# Sheet3.net
KiCad netlist of a schematic drawn in Altium Designer
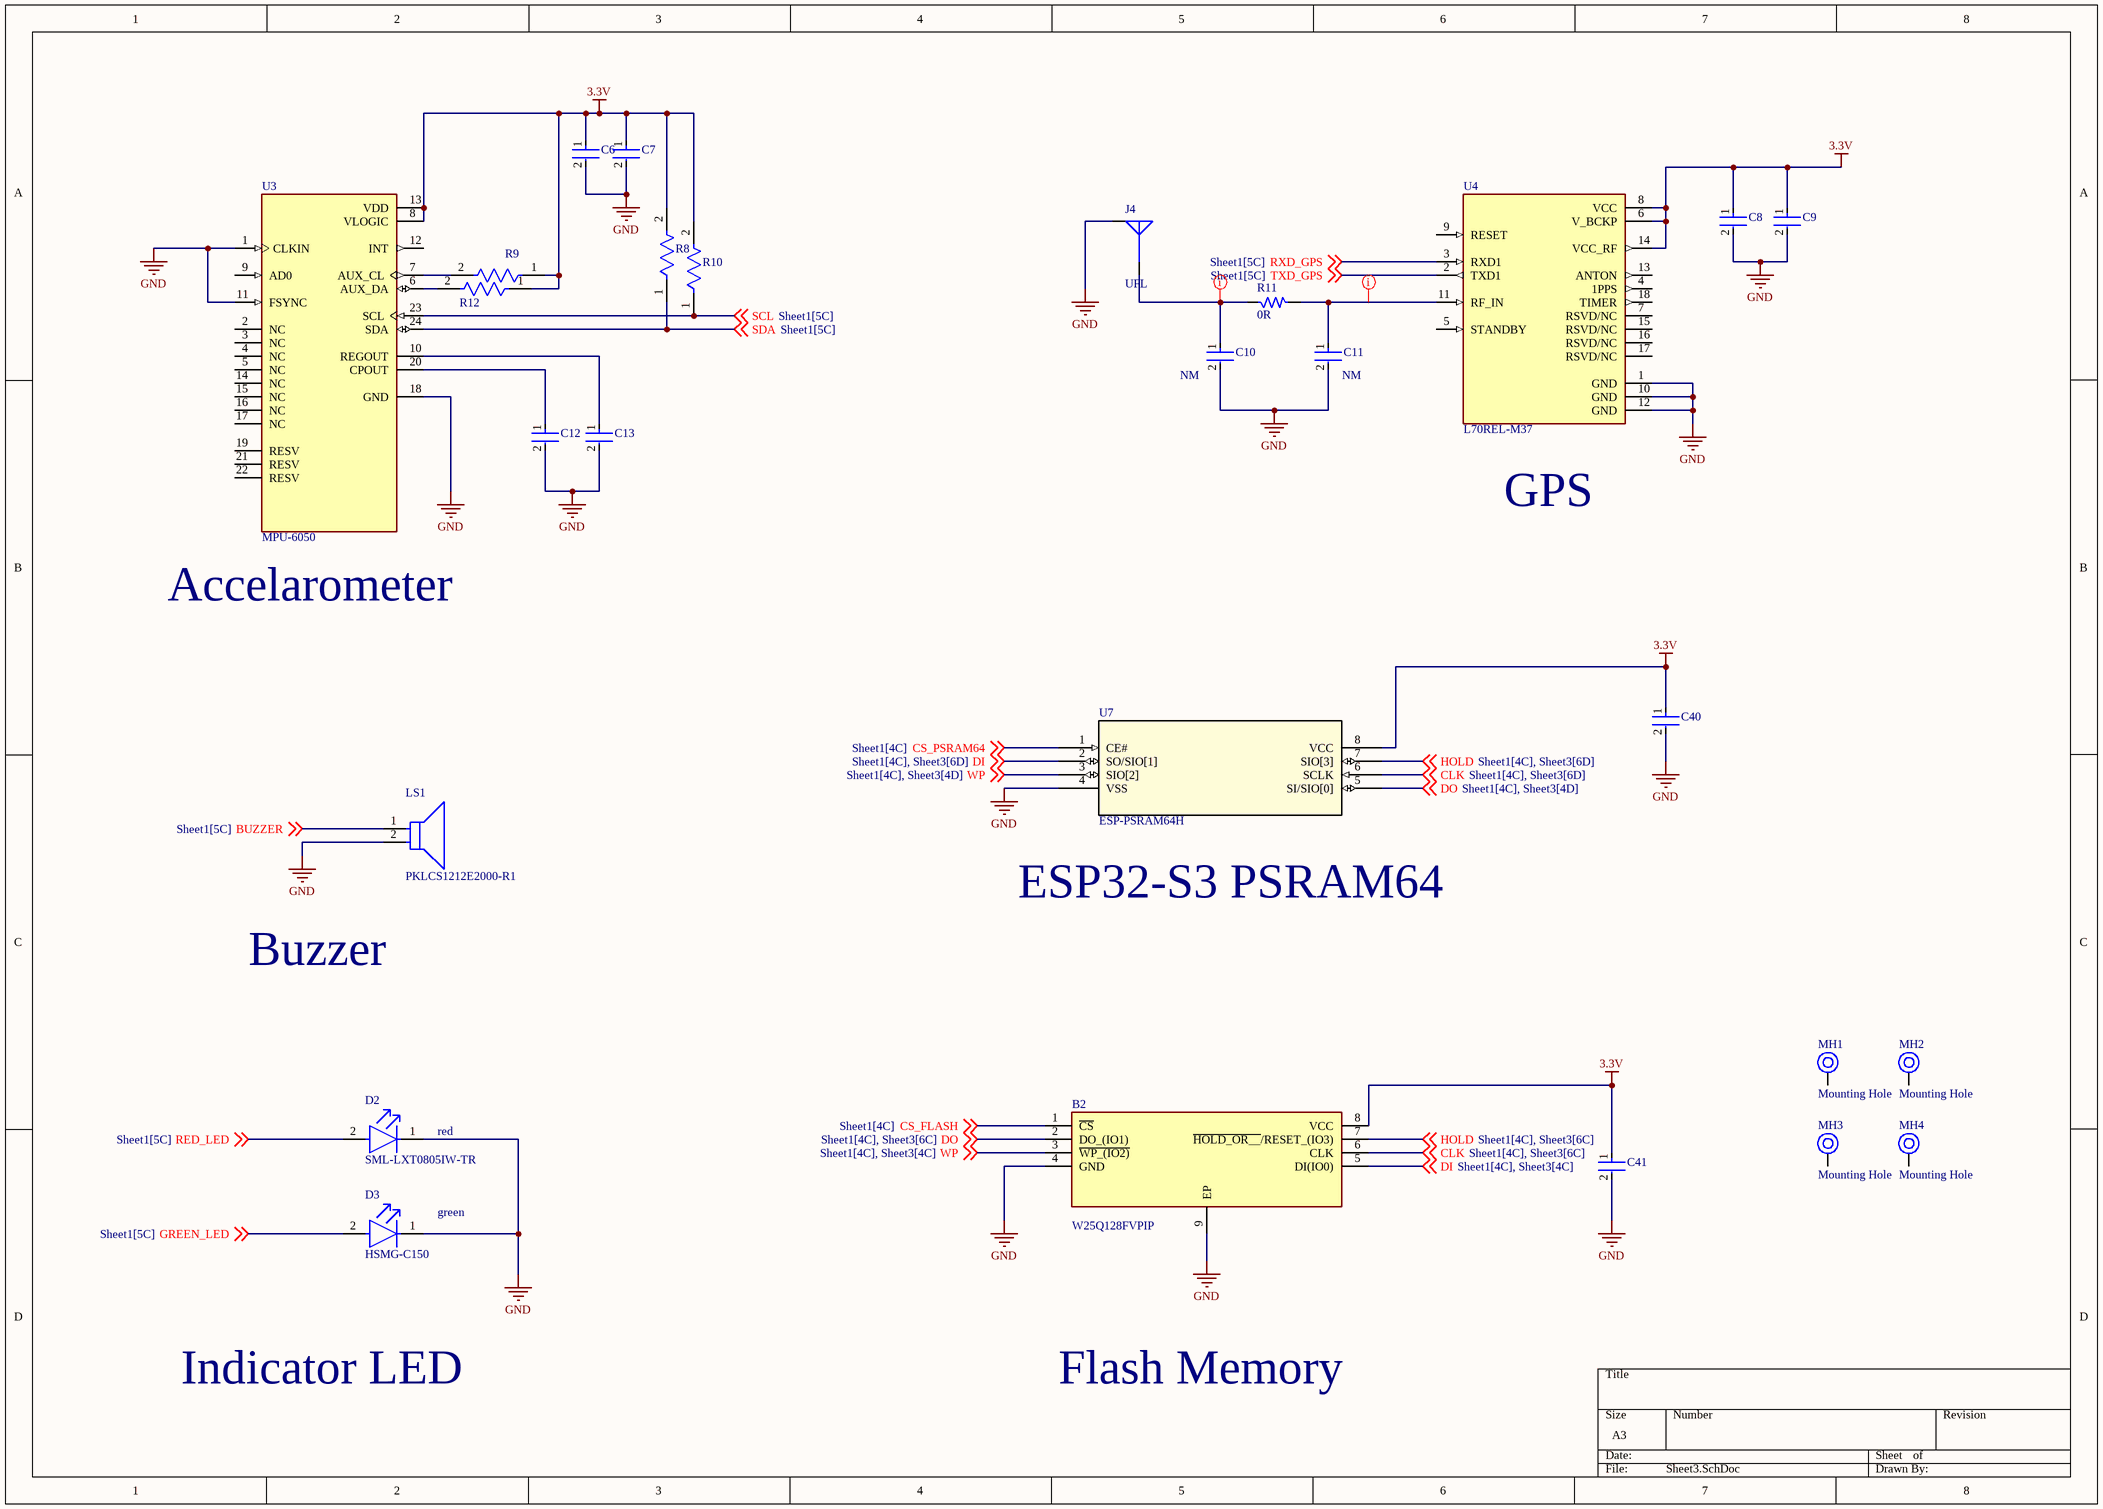
[diagram p0: Sheet3.SchDoc]

(export (version "E")
  (design (tool "Eeschema 10.0.6"))
  (components
    (comp (ref "B2")
      (value "W25Q128FVPIP")
      (footprint "SON127P600X500X80-9N-D")
      (description "3V 128M-BIT Serial Flash Memory With Dual/Quad SPI & QPI")
      (libsource (lib "W25Q128FVPIP") (part "W25Q128FVPIP"))
    )
    (comp (ref "C6")
      (value "C0402C104K4RACTU")
      (footprint "FP-C0402-BB-MFG")
      (description "CAP CER 0.1UF 16V X7R 0402")
      (fields
        (field (name "TOLERANCE") "0.1")
        (field (name "OCTOPART") "https://octopart.com/c0402c104k4ractu-kemet-94158")
      )
      (libsource (lib "Altium Content Vault") (part "b4654b650e69147ec39a6b967a45e02"))
    )
    (comp (ref "C7")
      (value "C0402C104K4RACTU")
      (footprint "FP-C0402-BB-MFG")
      (description "CAP CER 0.1UF 16V X7R 0402")
      (fields
        (field (name "TOLERANCE") "0.1")
        (field (name "OCTOPART") "https://octopart.com/c0402c104k4ractu-kemet-94158")
      )
      (libsource (lib "Altium Content Vault") (part "b4654b650e69147ec39a6b967a45e02"))
    )
    (comp (ref "C8")
      (value "C0402C104K4RACTU")
      (footprint "FP-C0402-BB-MFG")
      (description "CAP CER 0.1UF 16V X7R 0402")
      (fields
        (field (name "TOLERANCE") "0.1")
        (field (name "OCTOPART") "https://octopart.com/c0402c104k4ractu-kemet-94158")
      )
      (libsource (lib "Altium Content Vault") (part "b4654b650e69147ec39a6b967a45e02"))
    )
    (comp (ref "C9")
      (value "C0402C104K4RACTU")
      (footprint "FP-C0402-BB-MFG")
      (description "CAP CER 0.1UF 16V X7R 0402")
      (fields
        (field (name "TOLERANCE") "0.1")
        (field (name "OCTOPART") "https://octopart.com/c0402c104k4ractu-kemet-94158")
      )
      (libsource (lib "Altium Content Vault") (part "b4654b650e69147ec39a6b967a45e02"))
    )
    (comp (ref "C10")
      (value "04025C222KAT2A")
      (footprint "FP-0402-L_1_0_1-W_0_5_0_1-MFG")
      (description "General Purpose Ceramic Capacitor, 0402, 2.2nF, 10%, X7R, 15%, 50V")
      (fields (field (name "VOLTAGE") "50V") (field (name "TOLERANCE") "10%"))
      (libsource (lib "Altium Content Vault") (part "b4654b650e69147ec39a6b967a45e02"))
    )
    (comp (ref "C11")
      (value "C0402C104K4RACTU")
      (footprint "FP-C0402-BB-MFG")
      (description "CAP CER 0.1UF 16V X7R 0402")
      (fields
        (field (name "TOLERANCE") "0.1")
        (field (name "OCTOPART") "https://octopart.com/c0402c104k4ractu-kemet-94158")
      )
      (libsource (lib "Altium Content Vault") (part "b4654b650e69147ec39a6b967a45e02"))
    )
    (comp (ref "C12")
      (value "04025C222KAT2A")
      (footprint "FP-0402-L_1_0_1-W_0_5_0_1-MFG")
      (description "General Purpose Ceramic Capacitor, 0402, 2.2nF, 10%, X7R, 15%, 50V")
      (fields (field (name "VOLTAGE") "50V") (field (name "TOLERANCE") "10%"))
      (libsource (lib "Altium Content Vault") (part "b4654b650e69147ec39a6b967a45e02"))
    )
    (comp (ref "C13")
      (value "C0402C104K4RACTU")
      (footprint "FP-C0402-BB-MFG")
      (description "CAP CER 0.1UF 16V X7R 0402")
      (fields
        (field (name "TOLERANCE") "0.1")
        (field (name "OCTOPART") "https://octopart.com/c0402c104k4ractu-kemet-94158")
      )
      (libsource (lib "Altium Content Vault") (part "b4654b650e69147ec39a6b967a45e02"))
    )
    (comp (ref "C40")
      (value "C0402C104K4RACTU")
      (footprint "FP-C0402-BB-MFG")
      (description "CAP CER 0.1UF 16V X7R 0402")
      (fields
        (field (name "TOLERANCE") "0.1")
        (field (name "OCTOPART") "https://octopart.com/c0402c104k4ractu-kemet-94158")
      )
      (libsource (lib "Altium Content Vault") (part "b4654b650e69147ec39a6b967a45e02"))
    )
    (comp (ref "C41")
      (value "C0402C104K4RACTU")
      (footprint "FP-C0402-BB-MFG")
      (description "CAP CER 0.1UF 16V X7R 0402")
      (fields
        (field (name "TOLERANCE") "0.1")
        (field (name "OCTOPART") "https://octopart.com/c0402c104k4ractu-kemet-94158")
      )
      (libsource (lib "Altium Content Vault") (part "b4654b650e69147ec39a6b967a45e02"))
    )
    (comp (ref "D2")
      (value "SML-LXT0805IW-TR")
      (footprint "FP-SML-LXT0805IW-TR-MFG")
      (description "LED RED DIFFUSED SMD")
      (libsource (lib "Altium Content Vault") (part "8706943c75ba83719d021d2fdc84c58"))
    )
    (comp (ref "D3")
      (value "HSMG-C150")
      (footprint "FP-HSMG-C150-MFG")
      (description "LED GREEN DIFFUSED 1206 SMD")
      (fields
        (field (name "MANUFACTURER") "Broadcom")
        (field (name "OCTOPART") "https://octopart.com/hsmg-c150-broadcom-71131304")
      )
      (libsource (lib "Altium Content Vault") (part "8706943c75ba83719d021d2fdc84c58"))
    )
    (comp (ref "J4")
      (value "UFL")
      (footprint "MOLEX SD-734120110")
      (fields (field (name "PARTNUMBER") "MOLEX SD-734120110"))
      (libsource (lib "Conn RF") (part "UFL MOLEX SD-734120110"))
    )
    (comp (ref "LS1")
      (value "PKLCS1212E2000-R1")
      (footprint "FP-PKLCS1212E2000-R1-MFG")
      (description "AUDIO PIEZO TRANSDUCER 12.5V SMD")
      (fields
        (field (name "MANUFACTURER") "Murata")
        (field (name "OCTOPART") "https://octopart.com/pklcs1212e2000-r1-murata-7123179")
      )
      (libsource (lib "Altium Content Vault") (part "5f581d31613f872430949aa526fd155"))
    )
    (comp (ref "MH1")
      (value "Mounting Hole")
      (footprint "MOUNTING")
      (fields (field (name "MANUFACTURER PART NUMBER") "NA"))
      (libsource (lib "ESTEEMPCBLIB") (part "MH_3.5H_6D"))
    )
    (comp (ref "MH2")
      (value "Mounting Hole")
      (footprint "MOUNTING")
      (fields (field (name "MANUFACTURER PART NUMBER") "NA"))
      (libsource (lib "ESTEEMPCBLIB") (part "MH_3.5H_6D"))
    )
    (comp (ref "MH3")
      (value "Mounting Hole")
      (footprint "MOUNTING")
      (fields (field (name "MANUFACTURER PART NUMBER") "NA"))
      (libsource (lib "ESTEEMPCBLIB") (part "MH_3.5H_6D"))
    )
    (comp (ref "MH4")
      (value "Mounting Hole")
      (footprint "MOUNTING")
      (fields (field (name "MANUFACTURER PART NUMBER") "NA"))
      (libsource (lib "ESTEEMPCBLIB") (part "MH_3.5H_6D"))
    )
    (comp (ref "R8")
      (value "CRCW04024K70FKED")
      (footprint "FP-CRCW0402-e3-IPC_B")
      (description "RES Thick Film, 4.7kΩ, 1%, 0.063W, 100ppm/°C, 0402")
      (fields (field (name "TOLERANCE") "1%"))
      (libsource (lib "Altium Content Vault") (part "1029c3af85768c4190bb7ad29bc67b5"))
    )
    (comp (ref "R9")
      (value "CRCW04024K70FKED")
      (footprint "FP-CRCW0402-e3-IPC_B")
      (description "RES Thick Film, 4.7kΩ, 1%, 0.063W, 100ppm/°C, 0402")
      (fields (field (name "TOLERANCE") "1%"))
      (libsource (lib "Altium Content Vault") (part "1029c3af85768c4190bb7ad29bc67b5"))
    )
    (comp (ref "R10")
      (value "CRCW04024K70FKED")
      (footprint "FP-CRCW0402-e3-IPC_B")
      (description "RES Thick Film, 4.7kΩ, 1%, 0.063W, 100ppm/°C, 0402")
      (fields (field (name "TOLERANCE") "1%"))
      (libsource (lib "Altium Content Vault") (part "1029c3af85768c4190bb7ad29bc67b5"))
    )
    (comp (ref "R11")
      (value "0R")
      (footprint "RES_0805")
      (description "0 Ohms Jumper 0.125W, 1/8W Chip Resistor 0805 (2012 Metric) Automotive AEC-Q200 Thick Film")
      (fields (field (name "MANUFACTURER") "Walsin") (field (name "MANUFACTURER PART NUMBER") "WR08X000PTL"))
      (libsource (lib "ESTEEMPCBLIB") (part "RES_0R-0.125W-1%-0805"))
    )
    (comp (ref "R12")
      (value "CRCW04024K70FKED")
      (footprint "FP-CRCW0402-e3-IPC_B")
      (description "RES Thick Film, 4.7kΩ, 1%, 0.063W, 100ppm/°C, 0402")
      (fields (field (name "TOLERANCE") "1%"))
      (libsource (lib "Altium Content Vault") (part "1029c3af85768c4190bb7ad29bc67b5"))
    )
    (comp (ref "U3")
      (value "MPU-6050")
      (footprint "QFN50P400X400X95-24N")
      (description "MPU-6050 series Accelerometer, Gyroscope, 3 Axis Sensor Evaluation Board")
      (fields (field (name "MF") "TDK InvenSense"))
      (libsource (lib "MPU-6050") (part "MPU-6050"))
    )
    (comp (ref "U4")
      (value "L70REL-M37")
      (footprint "XCVR_L70REL-M37")
      (description "Navigation GPS Transceiver Module 1.575GHz Antenna Not Included Surface Mount")
      (fields (field (name "MF") "Quectel"))
      (libsource (lib "GPS") (part "L70REL-M37"))
    )
    (comp (ref "U7")
      (value "ESP-PSRAM64H")
      (footprint "SOP8-150MIL_ADA")
      (description "No Description Available")
      (libsource (lib "ESPRESSIFESP-PSRAM64H") (part "ESPRESSIF ESP-PSRAM64H"))
    )
  )
  (nets
    (net (code "1") (name "3.3V") (class "Default")
      (node (ref "B2") (pin "8") (pinfunction "VCC_8") (pintype "passive"))
      (node (ref "C40") (pin "1") (pinfunction "1_1") (pintype "passive"))
      (node (ref "C41") (pin "1") (pinfunction "1_1") (pintype "passive"))
      (node (ref "C6") (pin "1") (pinfunction "1_1") (pintype "passive"))
      (node (ref "C7") (pin "1") (pinfunction "1_1") (pintype "passive"))
      (node (ref "C8") (pin "1") (pinfunction "1_1") (pintype "passive"))
      (node (ref "C9") (pin "1") (pinfunction "1_1") (pintype "passive"))
      (node (ref "R10") (pin "2") (pinfunction "2_2") (pintype "passive"))
      (node (ref "R12") (pin "1") (pinfunction "1_1") (pintype "passive"))
      (node (ref "R8") (pin "2") (pinfunction "2_2") (pintype "passive"))
      (node (ref "R9") (pin "1") (pinfunction "1_1") (pintype "passive"))
      (node (ref "U3") (pin "13") (pinfunction "VDD_13") (pintype "power_in"))
      (node (ref "U3") (pin "8") (pinfunction "VLOGIC_8") (pintype "power_in"))
      (node (ref "U4") (pin "14") (pinfunction "VCC_RF_14") (pintype "output"))
      (node (ref "U4") (pin "6") (pinfunction "V_BCKP_6") (pintype "power_in"))
      (node (ref "U4") (pin "8") (pinfunction "VCC_8") (pintype "power_in"))
      (node (ref "U7") (pin "8") (pinfunction "VCC_8") (pintype "power_in"))
    )
    (net (code "2") (name "BUZZER") (class "Default")
      (node (ref "LS1") (pin "1") (pinfunction "1_1") (pintype "passive"))
    )
    (net (code "3") (name "CLK") (class "Default")
      (node (ref "B2") (pin "6") (pinfunction "CLK_6") (pintype "passive"))
      (node (ref "U7") (pin "6") (pinfunction "SCLK_6") (pintype "input"))
    )
    (net (code "4") (name "CS_FLASH") (class "Default")
      (node (ref "B2") (pin "1") (pinfunction "~{CS}_1") (pintype "passive"))
    )
    (net (code "5") (name "CS_PSRAM64") (class "Default")
      (node (ref "U7") (pin "1") (pinfunction "CE#_1") (pintype "input"))
    )
    (net (code "6") (name "DI") (class "Default")
      (node (ref "B2") (pin "5") (pinfunction "DI(IO0)_5") (pintype "passive"))
      (node (ref "U7") (pin "2") (pinfunction "SO/SIO[1]_2") (pintype "bidirectional"))
    )
    (net (code "7") (name "DO") (class "Default")
      (node (ref "B2") (pin "2") (pinfunction "DO_(IO1)_2") (pintype "passive"))
      (node (ref "U7") (pin "5") (pinfunction "SI/SIO[0]_5") (pintype "bidirectional"))
    )
    (net (code "8") (name "GND") (class "Default")
      (node (ref "B2") (pin "4") (pinfunction "GND_4") (pintype "passive"))
      (node (ref "B2") (pin "9") (pinfunction "EP_9") (pintype "passive"))
      (node (ref "C10") (pin "2") (pinfunction "2_2") (pintype "passive"))
      (node (ref "C11") (pin "2") (pinfunction "2_2") (pintype "passive"))
      (node (ref "C12") (pin "2") (pinfunction "2_2") (pintype "passive"))
      (node (ref "C13") (pin "2") (pinfunction "2_2") (pintype "passive"))
      (node (ref "C40") (pin "2") (pinfunction "2_2") (pintype "passive"))
      (node (ref "C41") (pin "2") (pinfunction "2_2") (pintype "passive"))
      (node (ref "C6") (pin "2") (pinfunction "2_2") (pintype "passive"))
      (node (ref "C7") (pin "2") (pinfunction "2_2") (pintype "passive"))
      (node (ref "C8") (pin "2") (pinfunction "2_2") (pintype "passive"))
      (node (ref "C9") (pin "2") (pinfunction "2_2") (pintype "passive"))
      (node (ref "D2") (pin "1") (pinfunction "C_1") (pintype "passive"))
      (node (ref "D3") (pin "1") (pinfunction "C_1") (pintype "passive"))
      (node (ref "J4") (pin "G") (pinfunction "G_G") (pintype "passive"))
      (node (ref "LS1") (pin "2") (pinfunction "2_2") (pintype "passive"))
      (node (ref "U3") (pin "1") (pinfunction "CLKIN_1") (pintype "input"))
      (node (ref "U3") (pin "11") (pinfunction "FSYNC_11") (pintype "input"))
      (node (ref "U3") (pin "18") (pinfunction "GND_18") (pintype "power_in"))
      (node (ref "U4") (pin "1") (pinfunction "GND_1") (pintype "power_in"))
      (node (ref "U4") (pin "10") (pinfunction "GND_10") (pintype "power_in"))
      (node (ref "U4") (pin "12") (pinfunction "GND_12") (pintype "power_in"))
      (node (ref "U7") (pin "4") (pinfunction "VSS_4") (pintype "power_in"))
    )
    (net (code "9") (name "GREEN_LED") (class "Default")
      (node (ref "D3") (pin "2") (pinfunction "A_2") (pintype "passive"))
    )
    (net (code "10") (name "HOLD") (class "Default")
      (node (ref "B2") (pin "7") (pinfunction "~{HOLD_OR__}/RESET_(IO3)_7") (pintype "passive"))
      (node (ref "U7") (pin "7") (pinfunction "SIO[3]_7") (pintype "bidirectional"))
    )
    (net (code "11") (name "Net-(C10-Pad1)") (class "Default")
      (node (ref "C10") (pin "1") (pinfunction "1_1") (pintype "passive"))
      (node (ref "J4") (pin "S") (pinfunction "S_S") (pintype "passive"))
      (node (ref "R11") (pin "1") (pinfunction "1_1") (pintype "passive"))
    )
    (net (code "12") (name "Net-(U3-AUX_CL)") (class "Default")
      (node (ref "R9") (pin "2") (pinfunction "2_2") (pintype "passive"))
      (node (ref "U3") (pin "7") (pinfunction "AUX_CL_7") (pintype "output"))
    )
    (net (code "13") (name "Net-(U3-AUX_DA)") (class "Default")
      (node (ref "R12") (pin "2") (pinfunction "2_2") (pintype "passive"))
      (node (ref "U3") (pin "6") (pinfunction "AUX_DA_6") (pintype "bidirectional"))
    )
    (net (code "14") (name "Net-(U3-CPOUT)") (class "Default")
      (node (ref "C12") (pin "1") (pinfunction "1_1") (pintype "passive"))
      (node (ref "U3") (pin "20") (pinfunction "CPOUT_20") (pintype "passive"))
    )
    (net (code "15") (name "Net-(U3-REGOUT)") (class "Default")
      (node (ref "C13") (pin "1") (pinfunction "1_1") (pintype "passive"))
      (node (ref "U3") (pin "10") (pinfunction "REGOUT_10") (pintype "passive"))
    )
    (net (code "16") (name "Net-(U4-RF_IN)") (class "Default")
      (node (ref "C11") (pin "1") (pinfunction "1_1") (pintype "passive"))
      (node (ref "R11") (pin "2") (pinfunction "2_2") (pintype "passive"))
      (node (ref "U4") (pin "11") (pinfunction "RF_IN_11") (pintype "input"))
    )
    (net (code "17") (name "RED_LED") (class "Default")
      (node (ref "D2") (pin "2") (pinfunction "A_2") (pintype "passive"))
    )
    (net (code "18") (name "RXD_GPS") (class "Default")
      (node (ref "U4") (pin "3") (pinfunction "RXD1_3") (pintype "input"))
    )
    (net (code "19") (name "SCL") (class "Default")
      (node (ref "R10") (pin "1") (pinfunction "1_1") (pintype "passive"))
      (node (ref "U3") (pin "23") (pinfunction "SCL_23") (pintype "input"))
    )
    (net (code "20") (name "SDA") (class "Default")
      (node (ref "R8") (pin "1") (pinfunction "1_1") (pintype "passive"))
      (node (ref "U3") (pin "24") (pinfunction "SDA_24") (pintype "bidirectional"))
    )
    (net (code "21") (name "TXD_GPS") (class "Default")
      (node (ref "U4") (pin "2") (pinfunction "TXD1_2") (pintype "output"))
    )
    (net (code "22") (name "WP") (class "Default")
      (node (ref "B2") (pin "3") (pinfunction "~{WP_(IO2)}_3") (pintype "passive"))
      (node (ref "U7") (pin "3") (pinfunction "SIO[2]_3") (pintype "bidirectional"))
    )
    (net (code "23") (name "unconnected-(MH1-Pad1)") (class "Default")
      (node (ref "MH1") (pin "1") (pinfunction "1_1") (pintype "passive"))
    )
    (net (code "24") (name "unconnected-(MH2-Pad1)") (class "Default")
      (node (ref "MH2") (pin "1") (pinfunction "1_1") (pintype "passive"))
    )
    (net (code "25") (name "unconnected-(MH3-Pad1)") (class "Default")
      (node (ref "MH3") (pin "1") (pinfunction "1_1") (pintype "passive"))
    )
    (net (code "26") (name "unconnected-(MH4-Pad1)") (class "Default")
      (node (ref "MH4") (pin "1") (pinfunction "1_1") (pintype "passive"))
    )
    (net (code "27") (name "unconnected-(U3-AD0-Pad9)") (class "Default")
      (node (ref "U3") (pin "9") (pinfunction "AD0_9") (pintype "input"))
    )
    (net (code "28") (name "unconnected-(U3-INT-Pad12)") (class "Default")
      (node (ref "U3") (pin "12") (pinfunction "INT_12") (pintype "output"))
    )
    (net (code "29") (name "unconnected-(U3-NC-Pad2)") (class "Default")
      (node (ref "U3") (pin "2") (pinfunction "NC_2") (pintype "passive"))
    )
    (net (code "30") (name "unconnected-(U3-NC-Pad3)") (class "Default")
      (node (ref "U3") (pin "3") (pinfunction "NC_3") (pintype "passive"))
    )
    (net (code "31") (name "unconnected-(U3-NC-Pad4)") (class "Default")
      (node (ref "U3") (pin "4") (pinfunction "NC_4") (pintype "passive"))
    )
    (net (code "32") (name "unconnected-(U3-NC-Pad5)") (class "Default")
      (node (ref "U3") (pin "5") (pinfunction "NC_5") (pintype "passive"))
    )
    (net (code "33") (name "unconnected-(U3-NC-Pad14)") (class "Default")
      (node (ref "U3") (pin "14") (pinfunction "NC_14") (pintype "passive"))
    )
    (net (code "34") (name "unconnected-(U3-NC-Pad15)") (class "Default")
      (node (ref "U3") (pin "15") (pinfunction "NC_15") (pintype "passive"))
    )
    (net (code "35") (name "unconnected-(U3-NC-Pad16)") (class "Default")
      (node (ref "U3") (pin "16") (pinfunction "NC_16") (pintype "passive"))
    )
    (net (code "36") (name "unconnected-(U3-NC-Pad17)") (class "Default")
      (node (ref "U3") (pin "17") (pinfunction "NC_17") (pintype "passive"))
    )
    (net (code "37") (name "unconnected-(U3-RESV-Pad19)") (class "Default")
      (node (ref "U3") (pin "19") (pinfunction "RESV_19") (pintype "passive"))
    )
    (net (code "38") (name "unconnected-(U3-RESV-Pad21)") (class "Default")
      (node (ref "U3") (pin "21") (pinfunction "RESV_21") (pintype "passive"))
    )
    (net (code "39") (name "unconnected-(U3-RESV-Pad22)") (class "Default")
      (node (ref "U3") (pin "22") (pinfunction "RESV_22") (pintype "passive"))
    )
    (net (code "40") (name "unconnected-(U4-1PPS-Pad4)") (class "Default")
      (node (ref "U4") (pin "4") (pinfunction "1PPS_4") (pintype "output"))
    )
    (net (code "41") (name "unconnected-(U4-ANTON-Pad13)") (class "Default")
      (node (ref "U4") (pin "13") (pinfunction "ANTON_13") (pintype "output"))
    )
    (net (code "42") (name "unconnected-(U4-RESET-Pad9)") (class "Default")
      (node (ref "U4") (pin "9") (pinfunction "RESET_9") (pintype "input"))
    )
    (net (code "43") (name "unconnected-(U4-RSVD{slash}NC-Pad7)") (class "Default")
      (node (ref "U4") (pin "7") (pinfunction "RSVD/NC_7") (pintype "passive"))
    )
    (net (code "44") (name "unconnected-(U4-RSVD{slash}NC-Pad15)") (class "Default")
      (node (ref "U4") (pin "15") (pinfunction "RSVD/NC_15") (pintype "passive"))
    )
    (net (code "45") (name "unconnected-(U4-RSVD{slash}NC-Pad16)") (class "Default")
      (node (ref "U4") (pin "16") (pinfunction "RSVD/NC_16") (pintype "passive"))
    )
    (net (code "46") (name "unconnected-(U4-RSVD{slash}NC-Pad17)") (class "Default")
      (node (ref "U4") (pin "17") (pinfunction "RSVD/NC_17") (pintype "passive"))
    )
    (net (code "47") (name "unconnected-(U4-STANDBY-Pad5)") (class "Default")
      (node (ref "U4") (pin "5") (pinfunction "STANDBY_5") (pintype "input"))
    )
    (net (code "48") (name "unconnected-(U4-TIMER-Pad18)") (class "Default")
      (node (ref "U4") (pin "18") (pinfunction "TIMER_18") (pintype "output"))
    )
  )
)
